# Inteligentny_czujnik_pojemno_ciowy.net
KiCad netlist of a schematic drawn in EAGLE
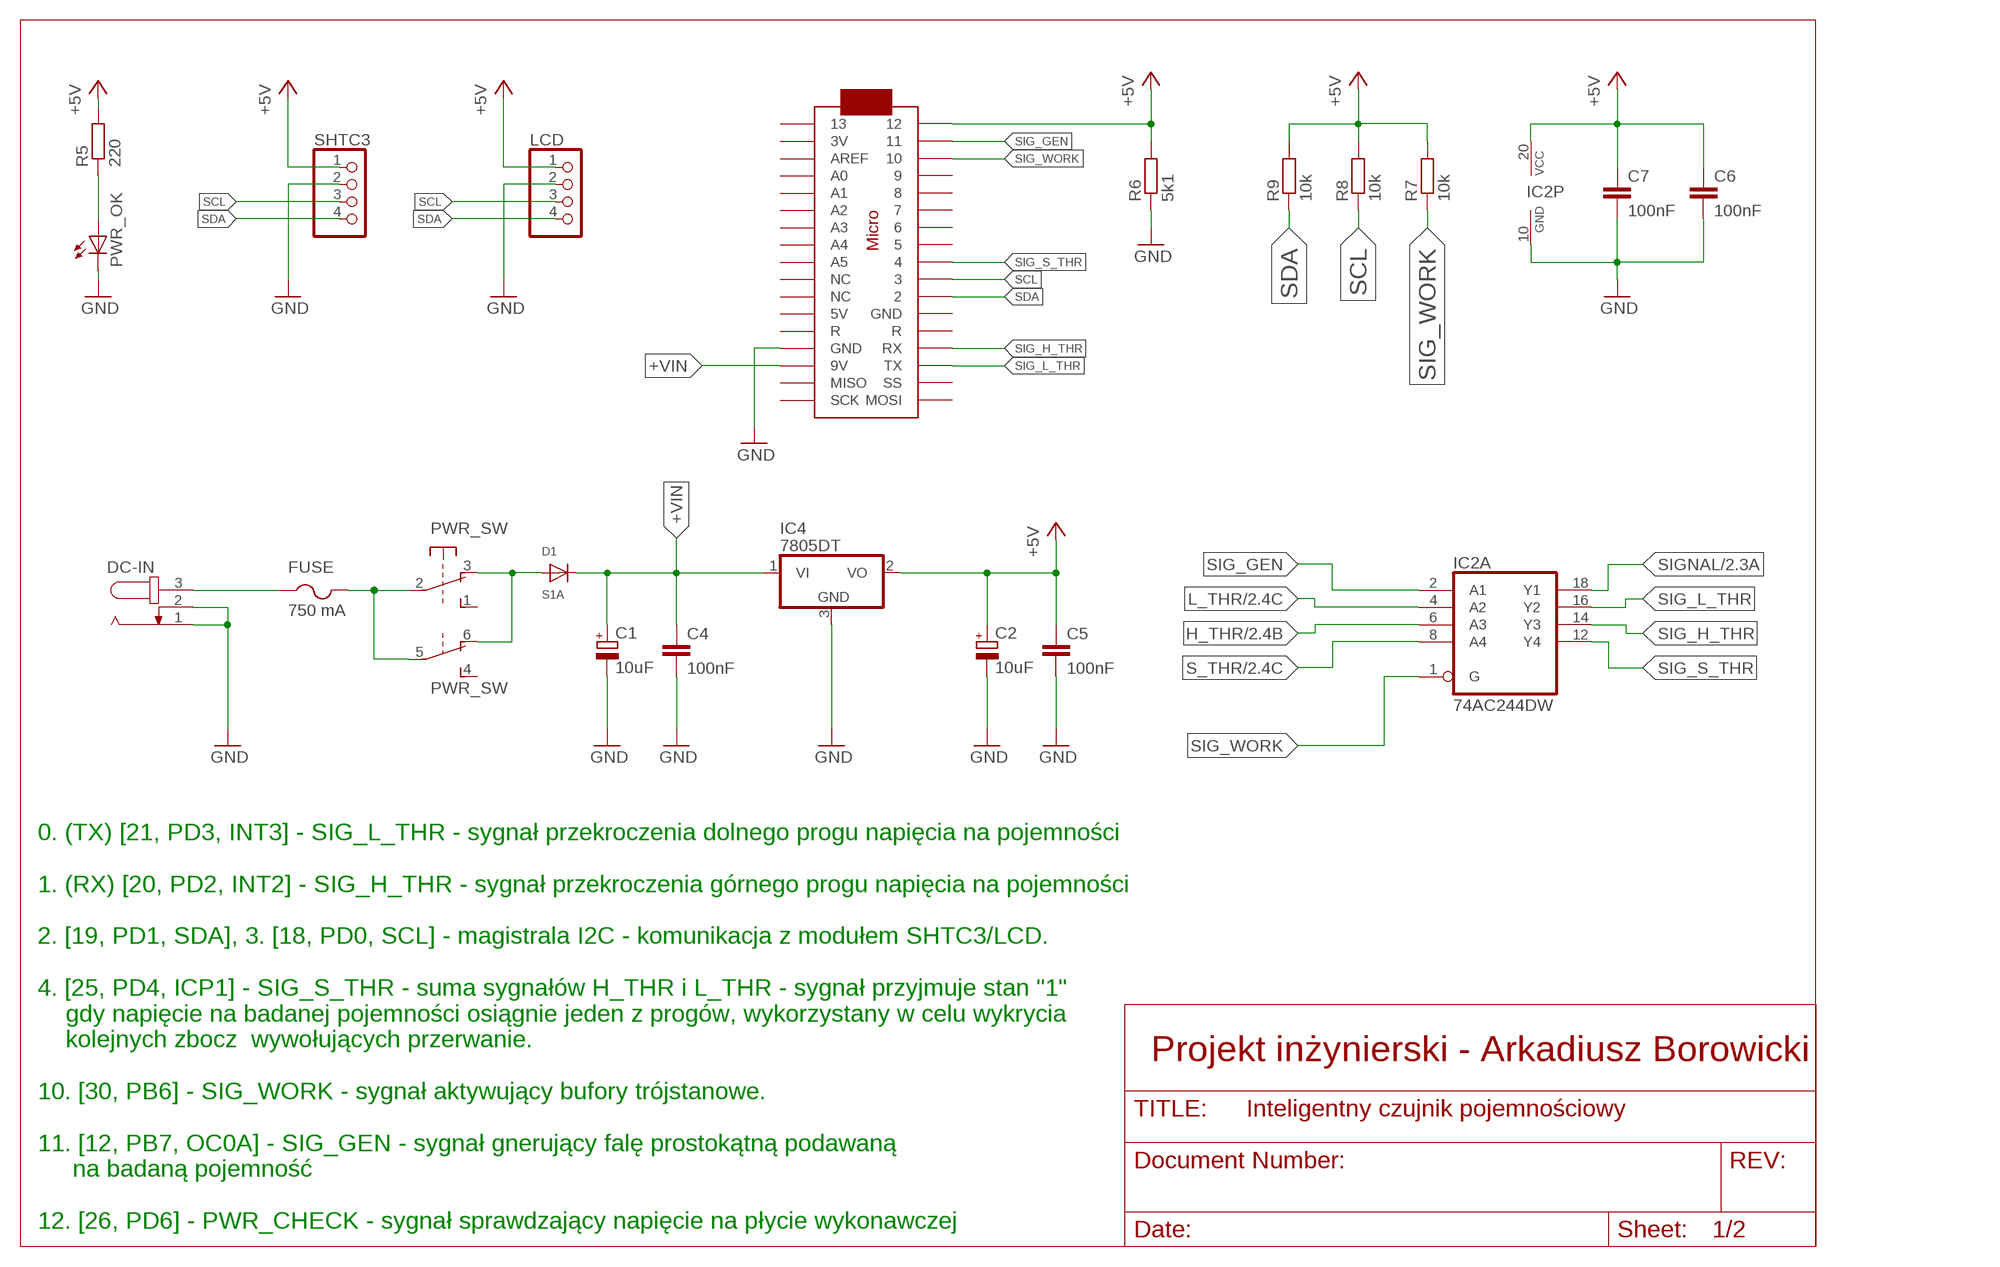
[diagram p0: schematic, sheet 1]
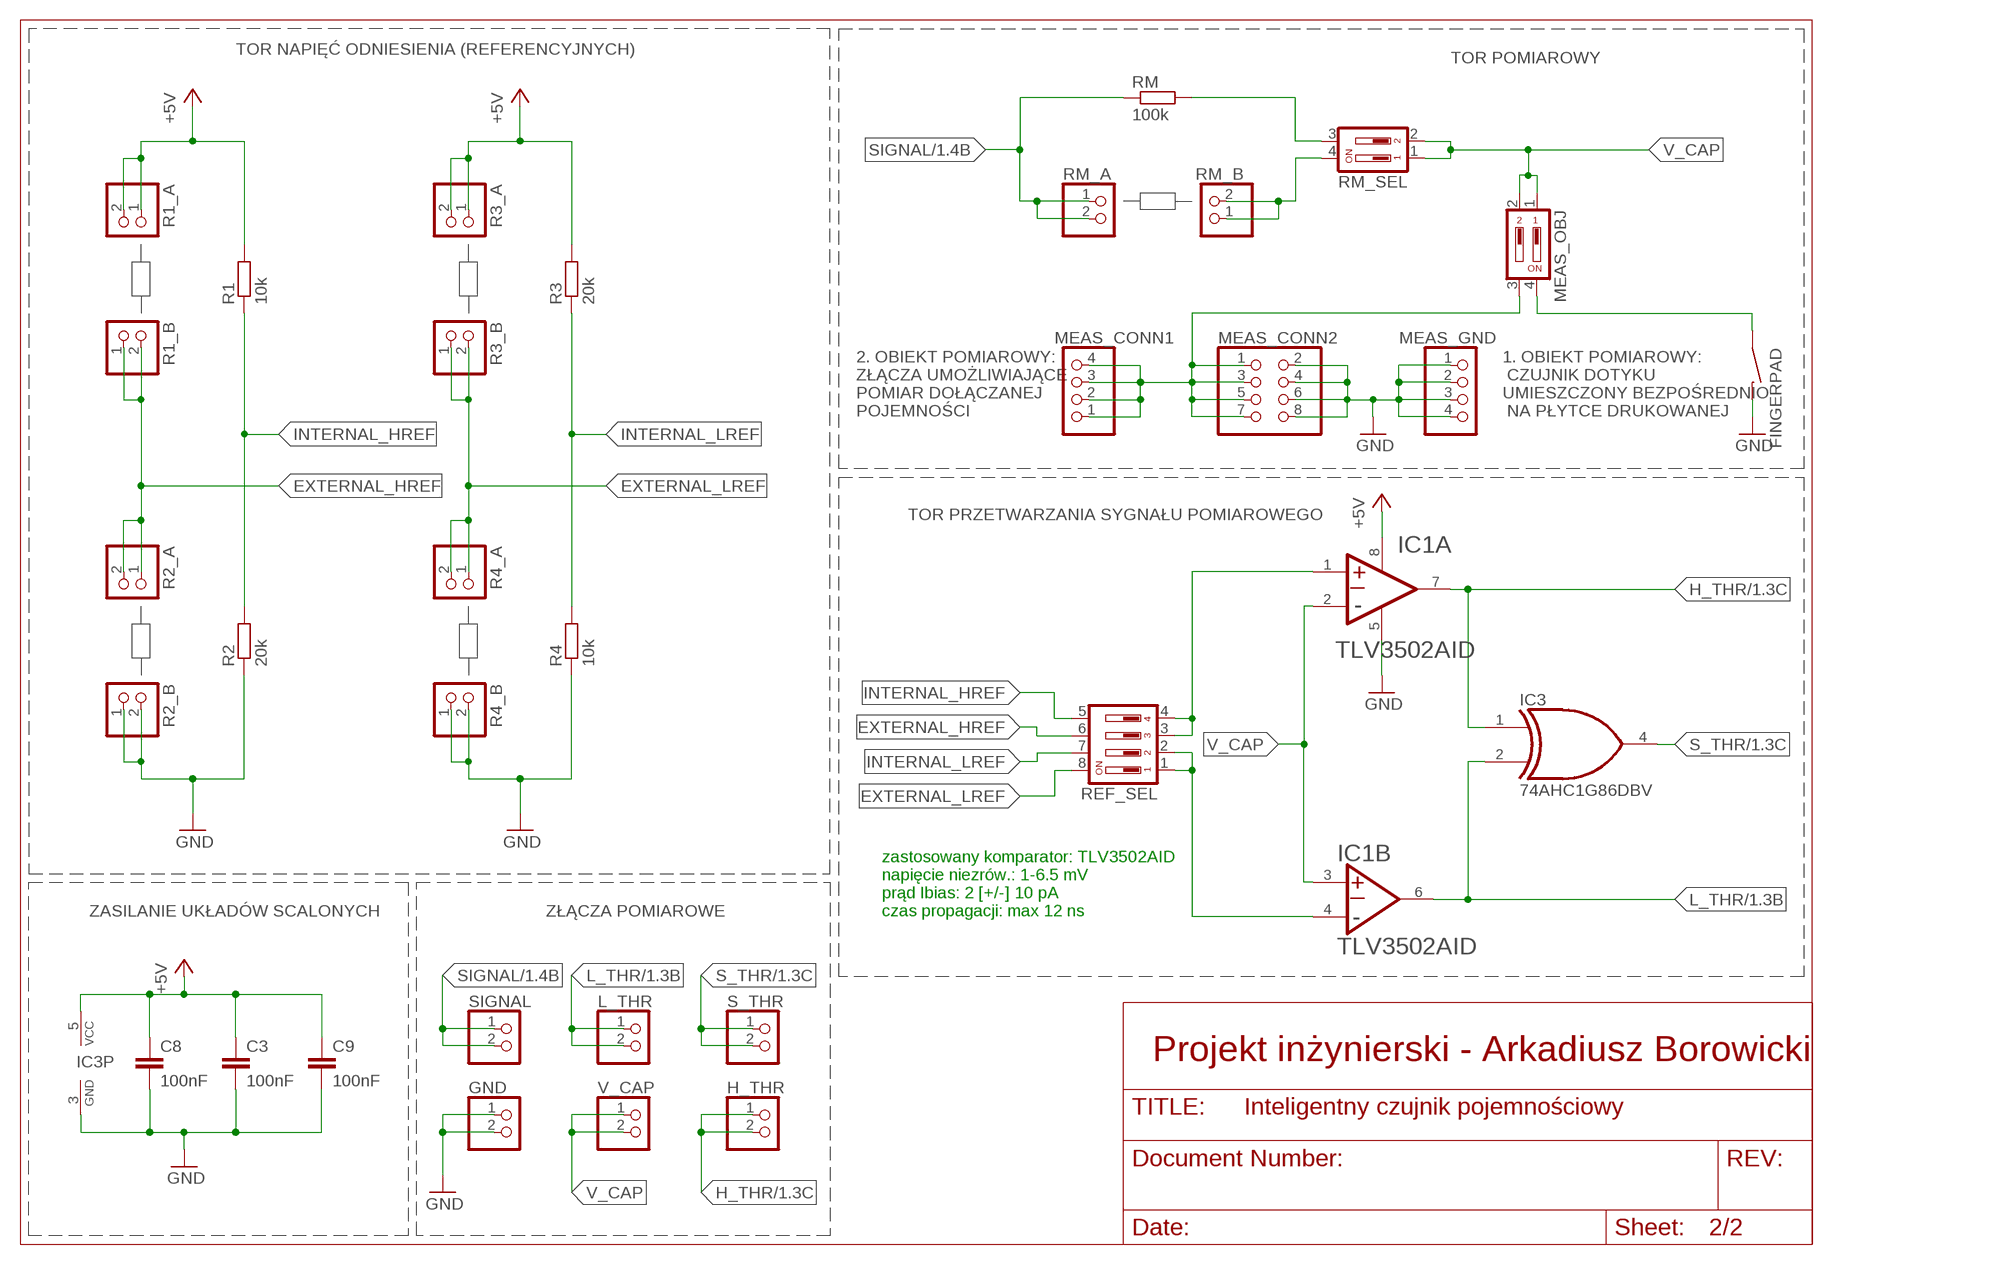
[diagram p1: schematic, sheet 2]

(export (version "E")
  (design (tool "Eeschema 10.0.6"))
  (components
    (comp (ref "C1")
      (value "10uF")
      (footprint "eagle-import:153CLV-0605")
      (libsource (lib "eagle-import") (part "CPOL-EU153CLV-0605"))
    )
    (comp (ref "C2")
      (value "10uF")
      (footprint "eagle-import:153CLV-0605")
      (libsource (lib "eagle-import") (part "CPOL-EU153CLV-0605"))
    )
    (comp (ref "C4")
      (value "100nF")
      (footprint "eagle-import:C1206K")
      (libsource (lib "eagle-import") (part "C-EUC1206K"))
    )
    (comp (ref "C5")
      (value "100nF")
      (footprint "eagle-import:C1206K")
      (libsource (lib "eagle-import") (part "C-EUC1206K"))
    )
    (comp (ref "C6")
      (value "100nF")
      (footprint "eagle-import:C1206K")
      (libsource (lib "eagle-import") (part "C-EUC1206K"))
    )
    (comp (ref "C7")
      (value "100nF")
      (footprint "eagle-import:C1206K")
      (libsource (lib "eagle-import") (part "C-EUC1206K"))
    )
    (comp (ref "D1")
      (value "S1A")
      (footprint "eagle-import:SMADIODE")
      (libsource (lib "eagle-import") (part "DIODESMA"))
    )
    (comp (ref "DC-IN")
      (value "JACK-PLUG1")
      (footprint "eagle-import:SPC4078")
      (libsource (lib "eagle-import") (part "JACK-PLUG1"))
    )
    (comp (ref "FUSE")
      (value "750 mA")
      (footprint "eagle-import:1812")
      (libsource (lib "eagle-import") (part "PTCFUSE-1812"))
    )
    (comp (ref "IC2")
      (value "74AC244DW")
      (footprint "eagle-import:SO20W")
      (libsource (lib "eagle-import") (part "74244DWAC"))
    )
    (comp (ref "IC4")
      (value "7805DT")
      (footprint "eagle-import:TO252")
      (libsource (lib "eagle-import") (part "78DT05"))
    )
    (comp (ref "LCD")
      (value "PINHD-1X4")
      (footprint "eagle-import:1X04")
      (libsource (lib "eagle-import") (part "PINHD-1X4"))
    )
    (comp (ref "PWR_OK")
      (value "LEDSMT1206")
      (footprint "eagle-import:1206")
      (libsource (lib "eagle-import") (part "LEDSMT1206"))
    )
    (comp (ref "PWR_SW")
      (value "9077-2")
      (footprint "eagle-import:9077-2")
      (libsource (lib "eagle-import") (part "9077-2"))
    )
    (comp (ref "R5")
      (value "220")
      (footprint "eagle-import:R1206")
      (libsource (lib "eagle-import") (part "R-EU_R1206"))
    )
    (comp (ref "R6")
      (value "5k1")
      (footprint "eagle-import:R1206")
      (libsource (lib "eagle-import") (part "R-EU_R1206"))
    )
    (comp (ref "R7")
      (value "10k")
      (footprint "eagle-import:R1206")
      (libsource (lib "eagle-import") (part "R-EU_R1206"))
    )
    (comp (ref "R8")
      (value "10k")
      (footprint "eagle-import:R1206")
      (libsource (lib "eagle-import") (part "R-EU_R1206"))
    )
    (comp (ref "R9")
      (value "10k")
      (footprint "eagle-import:R1206")
      (libsource (lib "eagle-import") (part "R-EU_R1206"))
    )
    (comp (ref "SHTC3")
      (value "PINHD-1X4")
      (footprint "eagle-import:1X04")
      (libsource (lib "eagle-import") (part "PINHD-1X4"))
    )
    (comp (ref "U$1")
      (value "ARDUINOMICRO")
      (footprint "eagle-import:ARDUINOMICRO")
      (libsource (lib "eagle-import") (part "ARDUINOMICRO"))
    )
    (comp (ref "C3")
      (value "100nF")
      (footprint "eagle-import:C1206K")
      (libsource (lib "eagle-import") (part "C-EUC1206K"))
    )
    (comp (ref "C8")
      (value "100nF")
      (footprint "eagle-import:C1206K")
      (libsource (lib "eagle-import") (part "C-EUC1206K"))
    )
    (comp (ref "C9")
      (value "100nF")
      (footprint "eagle-import:C1206K")
      (libsource (lib "eagle-import") (part "C-EUC1206K"))
    )
    (comp (ref "FINGERPAD")
      (value "FINGERPAD-2B")
      (footprint "eagle-import:FINGERPAD-2B")
      (libsource (lib "eagle-import") (part "FINGERPAD-2B"))
    )
    (comp (ref "GND")
      (value "PINHD-1X2")
      (footprint "eagle-import:1X02")
      (libsource (lib "eagle-import") (part "PINHD-1X2"))
    )
    (comp (ref "H_THR")
      (value "PINHD-1X2")
      (footprint "eagle-import:1X02")
      (libsource (lib "eagle-import") (part "PINHD-1X2"))
    )
    (comp (ref "IC1")
      (value "TEXAS_INSTRUMENTS_TLV3502AIDTEXAS_INSTRUMENTS_TLV3502AID_0_1")
      (footprint "eagle-import:TEXAS_INSTRUMENTS_TLV3502AID_1")
      (fields
        (field (name "DIGIKEY_PART_NUMBER") "296-18301-5-ND")
        (field (name "MF") "Texas Instruments")
        (field (name "MOUSER_PART_NUMBER") "595-TLV3502AID")
      )
      (libsource (lib "eagle-import") (part "TEXAS_INSTRUMENTS_TLV3502AIDTEXAS_INSTRUMENTS_TLV3502AID_0_1"))
    )
    (comp (ref "IC3")
      (value "74AHC1G86DBV")
      (footprint "eagle-import:SOT23-5")
      (libsource (lib "eagle-import") (part "741G86DBVAHC"))
    )
    (comp (ref "L_THR")
      (value "PINHD-1X2")
      (footprint "eagle-import:1X02")
      (libsource (lib "eagle-import") (part "PINHD-1X2"))
    )
    (comp (ref "MEAS_CONN1")
      (value "PINHD-1X4")
      (footprint "eagle-import:1X04")
      (libsource (lib "eagle-import") (part "PINHD-1X4"))
    )
    (comp (ref "MEAS_CONN2")
      (value "PINHD-2X4")
      (footprint "eagle-import:2X04")
      (libsource (lib "eagle-import") (part "PINHD-2X4"))
    )
    (comp (ref "MEAS_GND")
      (value "PINHD-1X4")
      (footprint "eagle-import:1X04")
      (libsource (lib "eagle-import") (part "PINHD-1X4"))
    )
    (comp (ref "MEAS_OBJ")
      (value "219-02")
      (footprint "eagle-import:CTS-219-02")
      (libsource (lib "eagle-import") (part "219-02"))
    )
    (comp (ref "R1")
      (value "10k")
      (footprint "eagle-import:M1206")
      (libsource (lib "eagle-import") (part "R-EU_M1206"))
    )
    (comp (ref "R1_A")
      (value "PINHD-1X2")
      (footprint "eagle-import:1X02")
      (libsource (lib "eagle-import") (part "PINHD-1X2"))
    )
    (comp (ref "R1_B")
      (value "PINHD-1X2")
      (footprint "eagle-import:1X02")
      (libsource (lib "eagle-import") (part "PINHD-1X2"))
    )
    (comp (ref "R2")
      (value "20k")
      (footprint "eagle-import:M1206")
      (libsource (lib "eagle-import") (part "R-EU_M1206"))
    )
    (comp (ref "R2_A")
      (value "PINHD-1X2")
      (footprint "eagle-import:1X02")
      (libsource (lib "eagle-import") (part "PINHD-1X2"))
    )
    (comp (ref "R2_B")
      (value "PINHD-1X2")
      (footprint "eagle-import:1X02")
      (libsource (lib "eagle-import") (part "PINHD-1X2"))
    )
    (comp (ref "R3")
      (value "20k")
      (footprint "eagle-import:M1206")
      (libsource (lib "eagle-import") (part "R-EU_M1206"))
    )
    (comp (ref "R3_A")
      (value "PINHD-1X2")
      (footprint "eagle-import:1X02")
      (libsource (lib "eagle-import") (part "PINHD-1X2"))
    )
    (comp (ref "R3_B")
      (value "PINHD-1X2")
      (footprint "eagle-import:1X02")
      (libsource (lib "eagle-import") (part "PINHD-1X2"))
    )
    (comp (ref "R4")
      (value "10k")
      (footprint "eagle-import:M1206")
      (libsource (lib "eagle-import") (part "R-EU_M1206"))
    )
    (comp (ref "R4_A")
      (value "PINHD-1X2")
      (footprint "eagle-import:1X02")
      (libsource (lib "eagle-import") (part "PINHD-1X2"))
    )
    (comp (ref "R4_B")
      (value "PINHD-1X2")
      (footprint "eagle-import:1X02")
      (libsource (lib "eagle-import") (part "PINHD-1X2"))
    )
    (comp (ref "REF_SEL")
      (value "219-04")
      (footprint "eagle-import:CTS-219-04")
      (libsource (lib "eagle-import") (part "219-04"))
    )
    (comp (ref "RM")
      (value "100k")
      (footprint "eagle-import:M1206")
      (libsource (lib "eagle-import") (part "R-EU_M1206"))
    )
    (comp (ref "RM_A")
      (value "PINHD-1X2")
      (footprint "eagle-import:1X02")
      (libsource (lib "eagle-import") (part "PINHD-1X2"))
    )
    (comp (ref "RM_B")
      (value "PINHD-1X2")
      (footprint "eagle-import:1X02")
      (libsource (lib "eagle-import") (part "PINHD-1X2"))
    )
    (comp (ref "RM_SEL")
      (value "219-02")
      (footprint "eagle-import:CTS-219-02")
      (libsource (lib "eagle-import") (part "219-02"))
    )
    (comp (ref "SIGNAL")
      (value "PINHD-1X2")
      (footprint "eagle-import:1X02")
      (libsource (lib "eagle-import") (part "PINHD-1X2"))
    )
    (comp (ref "S_THR")
      (value "PINHD-1X2")
      (footprint "eagle-import:1X02")
      (libsource (lib "eagle-import") (part "PINHD-1X2"))
    )
    (comp (ref "V_CAP")
      (value "PINHD-1X2")
      (footprint "eagle-import:1X02")
      (libsource (lib "eagle-import") (part "PINHD-1X2"))
    )
  )
  (nets
    (net (code "1") (name "+5V") (class "Default")
      (node (ref "C2") (pin "+") (pinfunction "+_+") (pintype "passive"))
      (node (ref "C3") (pin "1") (pinfunction "1_1") (pintype "passive"))
      (node (ref "C5") (pin "1") (pinfunction "1_1") (pintype "passive"))
      (node (ref "C6") (pin "1") (pinfunction "1_1") (pintype "passive"))
      (node (ref "C7") (pin "1") (pinfunction "1_1") (pintype "passive"))
      (node (ref "C8") (pin "1") (pinfunction "1_1") (pintype "passive"))
      (node (ref "C9") (pin "1") (pinfunction "1_1") (pintype "passive"))
      (node (ref "IC1") (pin "8") (pinfunction "V+_8") (pintype "power_in"))
      (node (ref "IC2") (pin "20") (pinfunction "VCC_20") (pintype "power_in"))
      (node (ref "IC3") (pin "5") (pinfunction "VCC_5") (pintype "power_in"))
      (node (ref "IC4") (pin "2") (pinfunction "VO_2") (pintype "passive"))
      (node (ref "LCD") (pin "1") (pinfunction "1_1") (pintype "passive"))
      (node (ref "R1") (pin "2") (pinfunction "2_2") (pintype "passive"))
      (node (ref "R1_A") (pin "1") (pinfunction "1_1") (pintype "passive"))
      (node (ref "R1_A") (pin "2") (pinfunction "2_2") (pintype "passive"))
      (node (ref "R3") (pin "2") (pinfunction "2_2") (pintype "passive"))
      (node (ref "R3_A") (pin "1") (pinfunction "1_1") (pintype "passive"))
      (node (ref "R3_A") (pin "2") (pinfunction "2_2") (pintype "passive"))
      (node (ref "R5") (pin "2") (pinfunction "2_2") (pintype "passive"))
      (node (ref "R6") (pin "2") (pinfunction "2_2") (pintype "passive"))
      (node (ref "R7") (pin "2") (pinfunction "2_2") (pintype "passive"))
      (node (ref "R8") (pin "2") (pinfunction "2_2") (pintype "passive"))
      (node (ref "R9") (pin "2") (pinfunction "2_2") (pintype "passive"))
      (node (ref "SHTC3") (pin "1") (pinfunction "1_1") (pintype "passive"))
      (node (ref "U$1") (pin "P$1") (pinfunction "12_P$1") (pintype "bidirectional"))
    )
    (net (code "2") (name "+VIN") (class "Default")
      (node (ref "C1") (pin "+") (pinfunction "+_+") (pintype "passive"))
      (node (ref "C4") (pin "1") (pinfunction "1_1") (pintype "passive"))
      (node (ref "D1") (pin "C") (pinfunction "C_C") (pintype "passive"))
      (node (ref "IC4") (pin "1") (pinfunction "VI_1") (pintype "input"))
      (node (ref "U$1") (pin "P$20") (pinfunction "9V_P$20") (pintype "bidirectional"))
    )
    (net (code "3") (name "EXTERNAL_HREF") (class "Default")
      (node (ref "R1_B") (pin "1") (pinfunction "1_1") (pintype "passive"))
      (node (ref "R1_B") (pin "2") (pinfunction "2_2") (pintype "passive"))
      (node (ref "R2_A") (pin "1") (pinfunction "1_1") (pintype "passive"))
      (node (ref "R2_A") (pin "2") (pinfunction "2_2") (pintype "passive"))
      (node (ref "REF_SEL") (pin "6") (pinfunction "6_6") (pintype "passive"))
    )
    (net (code "4") (name "EXTERNAL_LREF") (class "Default")
      (node (ref "R3_B") (pin "1") (pinfunction "1_1") (pintype "passive"))
      (node (ref "R3_B") (pin "2") (pinfunction "2_2") (pintype "passive"))
      (node (ref "R4_A") (pin "1") (pinfunction "1_1") (pintype "passive"))
      (node (ref "R4_A") (pin "2") (pinfunction "2_2") (pintype "passive"))
      (node (ref "REF_SEL") (pin "8") (pinfunction "8_8") (pintype "passive"))
    )
    (net (code "5") (name "GND") (class "Default")
      (node (ref "C1") (pin "-") (pinfunction "-_-") (pintype "passive"))
      (node (ref "C2") (pin "-") (pinfunction "-_-") (pintype "passive"))
      (node (ref "C3") (pin "2") (pinfunction "2_2") (pintype "passive"))
      (node (ref "C4") (pin "2") (pinfunction "2_2") (pintype "passive"))
      (node (ref "C5") (pin "2") (pinfunction "2_2") (pintype "passive"))
      (node (ref "C6") (pin "2") (pinfunction "2_2") (pintype "passive"))
      (node (ref "C7") (pin "2") (pinfunction "2_2") (pintype "passive"))
      (node (ref "C8") (pin "2") (pinfunction "2_2") (pintype "passive"))
      (node (ref "C9") (pin "2") (pinfunction "2_2") (pintype "passive"))
      (node (ref "DC-IN") (pin "1") (pinfunction "1_1") (pintype "passive"))
      (node (ref "DC-IN") (pin "2") (pinfunction "2_2") (pintype "passive"))
      (node (ref "FINGERPAD") (pin "2") (pinfunction "2_2") (pintype "passive"))
      (node (ref "GND") (pin "1") (pinfunction "1_1") (pintype "passive"))
      (node (ref "GND") (pin "2") (pinfunction "2_2") (pintype "passive"))
      (node (ref "IC1") (pin "5") (pinfunction "V−_5") (pintype "power_in"))
      (node (ref "IC2") (pin "10") (pinfunction "GND_10") (pintype "power_in"))
      (node (ref "IC3") (pin "3") (pinfunction "GND_3") (pintype "power_in"))
      (node (ref "IC4") (pin "3") (pinfunction "GND_3") (pintype "passive"))
      (node (ref "LCD") (pin "2") (pinfunction "2_2") (pintype "passive"))
      (node (ref "MEAS_CONN2") (pin "2") (pinfunction "2_2") (pintype "passive"))
      (node (ref "MEAS_CONN2") (pin "4") (pinfunction "4_4") (pintype "passive"))
      (node (ref "MEAS_CONN2") (pin "6") (pinfunction "6_6") (pintype "passive"))
      (node (ref "MEAS_CONN2") (pin "8") (pinfunction "8_8") (pintype "passive"))
      (node (ref "MEAS_GND") (pin "1") (pinfunction "1_1") (pintype "passive"))
      (node (ref "MEAS_GND") (pin "2") (pinfunction "2_2") (pintype "passive"))
      (node (ref "MEAS_GND") (pin "3") (pinfunction "3_3") (pintype "passive"))
      (node (ref "MEAS_GND") (pin "4") (pinfunction "4_4") (pintype "passive"))
      (node (ref "PWR_OK") (pin "C") (pinfunction "C_C") (pintype "passive"))
      (node (ref "R2") (pin "1") (pinfunction "1_1") (pintype "passive"))
      (node (ref "R2_B") (pin "1") (pinfunction "1_1") (pintype "passive"))
      (node (ref "R2_B") (pin "2") (pinfunction "2_2") (pintype "passive"))
      (node (ref "R4") (pin "1") (pinfunction "1_1") (pintype "passive"))
      (node (ref "R4_B") (pin "1") (pinfunction "1_1") (pintype "passive"))
      (node (ref "R4_B") (pin "2") (pinfunction "2_2") (pintype "passive"))
      (node (ref "R6") (pin "1") (pinfunction "1_1") (pintype "passive"))
      (node (ref "SHTC3") (pin "2") (pinfunction "2_2") (pintype "passive"))
      (node (ref "U$1") (pin "P$12") (pinfunction "GND_P$12") (pintype "bidirectional"))
    )
    (net (code "6") (name "H_THR") (class "Default")
      (node (ref "H_THR") (pin "1") (pinfunction "1_1") (pintype "passive"))
      (node (ref "H_THR") (pin "2") (pinfunction "2_2") (pintype "passive"))
      (node (ref "IC1") (pin "7") (pinfunction "OUT_A_7") (pintype "passive"))
      (node (ref "IC2") (pin "6") (pinfunction "A3_6") (pintype "input"))
      (node (ref "IC3") (pin "1") (pinfunction "I0_1") (pintype "input"))
    )
    (net (code "7") (name "INTERNAL_HREF") (class "Default")
      (node (ref "R1") (pin "1") (pinfunction "1_1") (pintype "passive"))
      (node (ref "R2") (pin "2") (pinfunction "2_2") (pintype "passive"))
      (node (ref "REF_SEL") (pin "5") (pinfunction "5_5") (pintype "passive"))
    )
    (net (code "8") (name "INTERNAL_LREF") (class "Default")
      (node (ref "R3") (pin "1") (pinfunction "1_1") (pintype "passive"))
      (node (ref "R4") (pin "2") (pinfunction "2_2") (pintype "passive"))
      (node (ref "REF_SEL") (pin "7") (pinfunction "7_7") (pintype "passive"))
    )
    (net (code "9") (name "L_THR") (class "Default")
      (node (ref "IC1") (pin "6") (pinfunction "OUT_B_6") (pintype "passive"))
      (node (ref "IC2") (pin "4") (pinfunction "A2_4") (pintype "input"))
      (node (ref "IC3") (pin "2") (pinfunction "I1_2") (pintype "input"))
      (node (ref "L_THR") (pin "1") (pinfunction "1_1") (pintype "passive"))
      (node (ref "L_THR") (pin "2") (pinfunction "2_2") (pintype "passive"))
    )
    (net (code "10") (name "Net-(DC-IN-Pad3)") (class "Default")
      (node (ref "DC-IN") (pin "3") (pinfunction "3_3") (pintype "passive"))
      (node (ref "FUSE") (pin "1") (pinfunction "1_1") (pintype "passive"))
    )
    (net (code "11") (name "Net-(FINGERPAD-Pad1)") (class "Default")
      (node (ref "FINGERPAD") (pin "1") (pinfunction "1_1") (pintype "passive"))
      (node (ref "MEAS_OBJ") (pin "4") (pinfunction "4_4") (pintype "passive"))
    )
    (net (code "12") (name "Net-(IC1A-+IN_A)") (class "Default")
      (node (ref "IC1") (pin "1") (pinfunction "+IN_A_1") (pintype "tri_state"))
      (node (ref "REF_SEL") (pin "3") (pinfunction "3_3") (pintype "passive"))
      (node (ref "REF_SEL") (pin "4") (pinfunction "4_4") (pintype "passive"))
    )
    (net (code "13") (name "Net-(IC1B-−IN_B)") (class "Default")
      (node (ref "IC1") (pin "4") (pinfunction "−IN_B_4") (pintype "tri_state"))
      (node (ref "REF_SEL") (pin "1") (pinfunction "1_1") (pintype "passive"))
      (node (ref "REF_SEL") (pin "2") (pinfunction "2_2") (pintype "passive"))
    )
    (net (code "14") (name "Net-(MEAS_CONN1-Pad1)") (class "Default")
      (node (ref "MEAS_CONN1") (pin "1") (pinfunction "1_1") (pintype "passive"))
      (node (ref "MEAS_CONN1") (pin "2") (pinfunction "2_2") (pintype "passive"))
      (node (ref "MEAS_CONN1") (pin "3") (pinfunction "3_3") (pintype "passive"))
      (node (ref "MEAS_CONN1") (pin "4") (pinfunction "4_4") (pintype "passive"))
      (node (ref "MEAS_CONN2") (pin "1") (pinfunction "1_1") (pintype "passive"))
      (node (ref "MEAS_CONN2") (pin "3") (pinfunction "3_3") (pintype "passive"))
      (node (ref "MEAS_CONN2") (pin "5") (pinfunction "5_5") (pintype "passive"))
      (node (ref "MEAS_CONN2") (pin "7") (pinfunction "7_7") (pintype "passive"))
      (node (ref "MEAS_OBJ") (pin "3") (pinfunction "3_3") (pintype "passive"))
    )
    (net (code "15") (name "Net-(PWR_OK-PadA)") (class "Default")
      (node (ref "PWR_OK") (pin "A") (pinfunction "A_A") (pintype "passive"))
      (node (ref "R5") (pin "1") (pinfunction "1_1") (pintype "passive"))
    )
    (net (code "16") (name "Net-(PWR_SWA-O)") (class "Default")
      (node (ref "D1") (pin "A") (pinfunction "A_A") (pintype "passive"))
      (node (ref "PWR_SW") (pin "3") (pinfunction "O_3") (pintype "passive"))
      (node (ref "PWR_SW") (pin "6") (pinfunction "O_6") (pintype "passive"))
    )
    (net (code "17") (name "Net-(PWR_SWA-P)") (class "Default")
      (node (ref "FUSE") (pin "2") (pinfunction "2_2") (pintype "passive"))
      (node (ref "PWR_SW") (pin "2") (pinfunction "P_2") (pintype "passive"))
      (node (ref "PWR_SW") (pin "5") (pinfunction "P_5") (pintype "passive"))
    )
    (net (code "18") (name "Net-(RM-Pad2)") (class "Default")
      (node (ref "RM") (pin "2") (pinfunction "2_2") (pintype "passive"))
      (node (ref "RM_SEL") (pin "3") (pinfunction "3_3") (pintype "passive"))
    )
    (net (code "19") (name "Net-(RM_B-Pad1)") (class "Default")
      (node (ref "RM_B") (pin "1") (pinfunction "1_1") (pintype "passive"))
      (node (ref "RM_B") (pin "2") (pinfunction "2_2") (pintype "passive"))
      (node (ref "RM_SEL") (pin "4") (pinfunction "4_4") (pintype "passive"))
    )
    (net (code "20") (name "SCL") (class "Default")
      (node (ref "LCD") (pin "3") (pinfunction "3_3") (pintype "passive"))
      (node (ref "R8") (pin "1") (pinfunction "1_1") (pintype "passive"))
      (node (ref "SHTC3") (pin "3") (pinfunction "3_3") (pintype "passive"))
      (node (ref "U$1") (pin "P$10") (pinfunction "3_P$10") (pintype "bidirectional"))
    )
    (net (code "21") (name "SDA") (class "Default")
      (node (ref "LCD") (pin "4") (pinfunction "4_4") (pintype "passive"))
      (node (ref "R9") (pin "1") (pinfunction "1_1") (pintype "passive"))
      (node (ref "SHTC3") (pin "4") (pinfunction "4_4") (pintype "passive"))
      (node (ref "U$1") (pin "P$11") (pinfunction "2_P$11") (pintype "bidirectional"))
    )
    (net (code "22") (name "SIGNAL") (class "Default")
      (node (ref "IC2") (pin "18") (pinfunction "Y1_18") (pintype "tri_state"))
      (node (ref "RM") (pin "1") (pinfunction "1_1") (pintype "passive"))
      (node (ref "RM_A") (pin "1") (pinfunction "1_1") (pintype "passive"))
      (node (ref "RM_A") (pin "2") (pinfunction "2_2") (pintype "passive"))
      (node (ref "SIGNAL") (pin "1") (pinfunction "1_1") (pintype "passive"))
      (node (ref "SIGNAL") (pin "2") (pinfunction "2_2") (pintype "passive"))
    )
    (net (code "23") (name "SIG_GEN") (class "Default")
      (node (ref "IC2") (pin "2") (pinfunction "A1_2") (pintype "input"))
      (node (ref "U$1") (pin "P$2") (pinfunction "11_P$2") (pintype "bidirectional"))
    )
    (net (code "24") (name "SIG_H_THR") (class "Default")
      (node (ref "IC2") (pin "14") (pinfunction "Y3_14") (pintype "tri_state"))
      (node (ref "U$1") (pin "P$14") (pinfunction "RX_P$14") (pintype "bidirectional"))
    )
    (net (code "25") (name "SIG_L_THR") (class "Default")
      (node (ref "IC2") (pin "16") (pinfunction "Y2_16") (pintype "tri_state"))
      (node (ref "U$1") (pin "P$15") (pinfunction "TX_P$15") (pintype "bidirectional"))
    )
    (net (code "26") (name "SIG_S_THR") (class "Default")
      (node (ref "IC2") (pin "12") (pinfunction "Y4_12") (pintype "tri_state"))
      (node (ref "U$1") (pin "P$9") (pinfunction "4_P$9") (pintype "bidirectional"))
    )
    (net (code "27") (name "SIG_WORK") (class "Default")
      (node (ref "IC2") (pin "1") (pinfunction "G_1") (pintype "input"))
      (node (ref "R7") (pin "1") (pinfunction "1_1") (pintype "passive"))
      (node (ref "U$1") (pin "P$3") (pinfunction "10_P$3") (pintype "bidirectional"))
    )
    (net (code "28") (name "S_THR") (class "Default")
      (node (ref "IC2") (pin "8") (pinfunction "A4_8") (pintype "input"))
      (node (ref "IC3") (pin "4") (pinfunction "O_4") (pintype "output"))
      (node (ref "S_THR") (pin "1") (pinfunction "1_1") (pintype "passive"))
      (node (ref "S_THR") (pin "2") (pinfunction "2_2") (pintype "passive"))
    )
    (net (code "29") (name "V_CAP") (class "Default")
      (node (ref "IC1") (pin "2") (pinfunction "−IN_A_2") (pintype "tri_state"))
      (node (ref "IC1") (pin "3") (pinfunction "+IN_B_3") (pintype "tri_state"))
      (node (ref "MEAS_OBJ") (pin "1") (pinfunction "1_1") (pintype "passive"))
      (node (ref "MEAS_OBJ") (pin "2") (pinfunction "2_2") (pintype "passive"))
      (node (ref "RM_SEL") (pin "1") (pinfunction "1_1") (pintype "passive"))
      (node (ref "RM_SEL") (pin "2") (pinfunction "2_2") (pintype "passive"))
      (node (ref "V_CAP") (pin "1") (pinfunction "1_1") (pintype "passive"))
      (node (ref "V_CAP") (pin "2") (pinfunction "2_2") (pintype "passive"))
    )
    (net (code "30") (name "unconnected-(PWR_SWA-S-Pad1)") (class "Default")
      (node (ref "PWR_SW") (pin "1") (pinfunction "S_1") (pintype "passive"))
    )
    (net (code "31") (name "unconnected-(PWR_SWB-S-Pad4)") (class "Default")
      (node (ref "PWR_SW") (pin "4") (pinfunction "S_4") (pintype "passive"))
    )
    (net (code "32") (name "unconnected-(U$1-3V-PadP$33)") (class "Default")
      (node (ref "U$1") (pin "P$33") (pinfunction "3V_P$33") (pintype "bidirectional"))
    )
    (net (code "33") (name "unconnected-(U$1-5-PadP$8)") (class "Default")
      (node (ref "U$1") (pin "P$8") (pinfunction "5_P$8") (pintype "bidirectional"))
    )
    (net (code "34") (name "unconnected-(U$1-5V-PadP$23)") (class "Default")
      (node (ref "U$1") (pin "P$23") (pinfunction "5V_P$23") (pintype "bidirectional"))
    )
    (net (code "35") (name "unconnected-(U$1-6-PadP$7)") (class "Default")
      (node (ref "U$1") (pin "P$7") (pinfunction "6_P$7") (pintype "bidirectional"))
    )
    (net (code "36") (name "unconnected-(U$1-7-PadP$6)") (class "Default")
      (node (ref "U$1") (pin "P$6") (pinfunction "7_P$6") (pintype "bidirectional"))
    )
    (net (code "37") (name "unconnected-(U$1-8-PadP$5)") (class "Default")
      (node (ref "U$1") (pin "P$5") (pinfunction "8_P$5") (pintype "bidirectional"))
    )
    (net (code "38") (name "unconnected-(U$1-9-PadP$4)") (class "Default")
      (node (ref "U$1") (pin "P$4") (pinfunction "9_P$4") (pintype "bidirectional"))
    )
    (net (code "39") (name "unconnected-(U$1-13-PadP$34)") (class "Default")
      (node (ref "U$1") (pin "P$34") (pinfunction "13_P$34") (pintype "bidirectional"))
    )
    (net (code "40") (name "unconnected-(U$1-A0-PadP$31)") (class "Default")
      (node (ref "U$1") (pin "P$31") (pinfunction "A0_P$31") (pintype "bidirectional"))
    )
    (net (code "41") (name "unconnected-(U$1-A1-PadP$30)") (class "Default")
      (node (ref "U$1") (pin "P$30") (pinfunction "A1_P$30") (pintype "bidirectional"))
    )
    (net (code "42") (name "unconnected-(U$1-A2-PadP$29)") (class "Default")
      (node (ref "U$1") (pin "P$29") (pinfunction "A2_P$29") (pintype "bidirectional"))
    )
    (net (code "43") (name "unconnected-(U$1-A3-PadP$28)") (class "Default")
      (node (ref "U$1") (pin "P$28") (pinfunction "A3_P$28") (pintype "bidirectional"))
    )
    (net (code "44") (name "unconnected-(U$1-A4-PadP$27)") (class "Default")
      (node (ref "U$1") (pin "P$27") (pinfunction "A4_P$27") (pintype "bidirectional"))
    )
    (net (code "45") (name "unconnected-(U$1-A5-PadP$26)") (class "Default")
      (node (ref "U$1") (pin "P$26") (pinfunction "A5_P$26") (pintype "bidirectional"))
    )
    (net (code "46") (name "unconnected-(U$1-AREF-PadP$32)") (class "Default")
      (node (ref "U$1") (pin "P$32") (pinfunction "AREF_P$32") (pintype "bidirectional"))
    )
    (net (code "47") (name "unconnected-(U$1-GND-PadP$21)") (class "Default")
      (node (ref "U$1") (pin "P$21") (pinfunction "GND_P$21") (pintype "bidirectional"))
    )
    (net (code "48") (name "unconnected-(U$1-MISO-PadP$19)") (class "Default")
      (node (ref "U$1") (pin "P$19") (pinfunction "MISO_P$19") (pintype "bidirectional"))
    )
    (net (code "49") (name "unconnected-(U$1-MOSI-PadP$17)") (class "Default")
      (node (ref "U$1") (pin "P$17") (pinfunction "MOSI_P$17") (pintype "bidirectional"))
    )
    (net (code "50") (name "unconnected-(U$1-NC-PadP$24)") (class "Default")
      (node (ref "U$1") (pin "P$24") (pinfunction "NC_P$24") (pintype "bidirectional"))
    )
    (net (code "51") (name "unconnected-(U$1-NC-PadP$25)") (class "Default")
      (node (ref "U$1") (pin "P$25") (pinfunction "NC_P$25") (pintype "bidirectional"))
    )
    (net (code "52") (name "unconnected-(U$1-R-PadP$13)") (class "Default")
      (node (ref "U$1") (pin "P$13") (pinfunction "R_P$13") (pintype "bidirectional"))
    )
    (net (code "53") (name "unconnected-(U$1-R-PadP$22)") (class "Default")
      (node (ref "U$1") (pin "P$22") (pinfunction "R_P$22") (pintype "bidirectional"))
    )
    (net (code "54") (name "unconnected-(U$1-SCK-PadP$18)") (class "Default")
      (node (ref "U$1") (pin "P$18") (pinfunction "SCK_P$18") (pintype "bidirectional"))
    )
    (net (code "55") (name "unconnected-(U$1-SS-PadP$16)") (class "Default")
      (node (ref "U$1") (pin "P$16") (pinfunction "SS_P$16") (pintype "bidirectional"))
    )
  )
)
